# FAJAS_EDCPSU_USBC_single.net
KiCad netlist of a schematic drawn in EAGLE
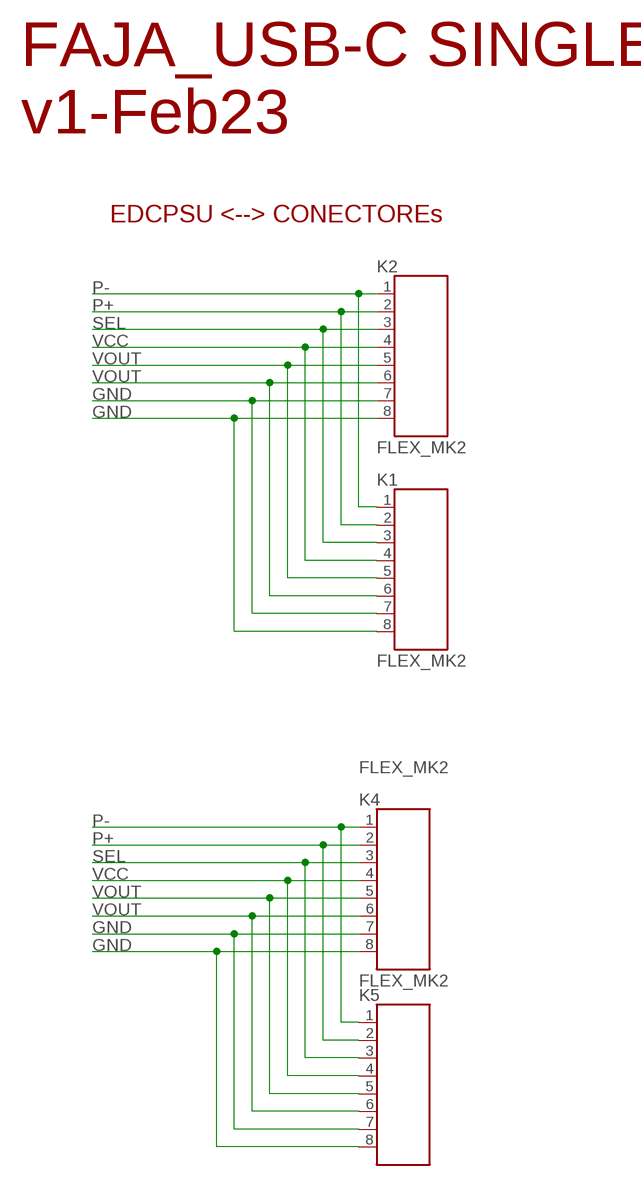
[diagram p0: schematic, sheet 1]

(export (version "E")
  (design (tool "Eeschema 10.0.6"))
  (components
    (comp (ref "K1")
      (value "FLEX_MK2")
      (footprint "eagle-import:FLEX8")
      (libsource (lib "eagle-import") (part "FLEX8"))
    )
    (comp (ref "K2")
      (value "FLEX_MK2")
      (footprint "eagle-import:FLEX8")
      (libsource (lib "eagle-import") (part "FLEX8"))
    )
    (comp (ref "K4")
      (value "FLEX_MK2")
      (footprint "eagle-import:FLEX8")
      (libsource (lib "eagle-import") (part "FLEX8"))
    )
    (comp (ref "K5")
      (value "FLEX_MK2")
      (footprint "eagle-import:FLEX8")
      (libsource (lib "eagle-import") (part "FLEX8"))
    )
  )
  (nets
    (net (code "1") (name "/GND") (class "Default")
      (node (ref "K1") (pin "7") (pinfunction "7_7") (pintype "passive"))
      (node (ref "K1") (pin "8") (pinfunction "8_8") (pintype "passive"))
      (node (ref "K2") (pin "7") (pinfunction "7_7") (pintype "passive"))
      (node (ref "K2") (pin "8") (pinfunction "8_8") (pintype "passive"))
      (node (ref "K4") (pin "7") (pinfunction "7_7") (pintype "passive"))
      (node (ref "K4") (pin "8") (pinfunction "8_8") (pintype "passive"))
      (node (ref "K5") (pin "7") (pinfunction "7_7") (pintype "passive"))
      (node (ref "K5") (pin "8") (pinfunction "8_8") (pintype "passive"))
    )
    (net (code "2") (name "/P+") (class "Default")
      (node (ref "K1") (pin "2") (pinfunction "2_2") (pintype "passive"))
      (node (ref "K2") (pin "2") (pinfunction "2_2") (pintype "passive"))
      (node (ref "K4") (pin "2") (pinfunction "2_2") (pintype "passive"))
      (node (ref "K5") (pin "2") (pinfunction "2_2") (pintype "passive"))
    )
    (net (code "3") (name "/P-") (class "Default")
      (node (ref "K1") (pin "1") (pinfunction "1_1") (pintype "passive"))
      (node (ref "K2") (pin "1") (pinfunction "1_1") (pintype "passive"))
      (node (ref "K4") (pin "1") (pinfunction "1_1") (pintype "passive"))
      (node (ref "K5") (pin "1") (pinfunction "1_1") (pintype "passive"))
    )
    (net (code "4") (name "/SEL") (class "Default")
      (node (ref "K1") (pin "3") (pinfunction "3_3") (pintype "passive"))
      (node (ref "K2") (pin "3") (pinfunction "3_3") (pintype "passive"))
      (node (ref "K4") (pin "3") (pinfunction "3_3") (pintype "passive"))
      (node (ref "K5") (pin "3") (pinfunction "3_3") (pintype "passive"))
    )
    (net (code "5") (name "/VCC") (class "Default")
      (node (ref "K1") (pin "4") (pinfunction "4_4") (pintype "passive"))
      (node (ref "K2") (pin "4") (pinfunction "4_4") (pintype "passive"))
      (node (ref "K4") (pin "4") (pinfunction "4_4") (pintype "passive"))
      (node (ref "K5") (pin "4") (pinfunction "4_4") (pintype "passive"))
    )
    (net (code "6") (name "/VOUT") (class "Default")
      (node (ref "K1") (pin "5") (pinfunction "5_5") (pintype "passive"))
      (node (ref "K1") (pin "6") (pinfunction "6_6") (pintype "passive"))
      (node (ref "K2") (pin "5") (pinfunction "5_5") (pintype "passive"))
      (node (ref "K2") (pin "6") (pinfunction "6_6") (pintype "passive"))
      (node (ref "K4") (pin "5") (pinfunction "5_5") (pintype "passive"))
      (node (ref "K4") (pin "6") (pinfunction "6_6") (pintype "passive"))
      (node (ref "K5") (pin "5") (pinfunction "5_5") (pintype "passive"))
      (node (ref "K5") (pin "6") (pinfunction "6_6") (pintype "passive"))
    )
  )
)
